# STorM32_NT_logger_v11.net
KiCad netlist of a schematic drawn in EAGLE
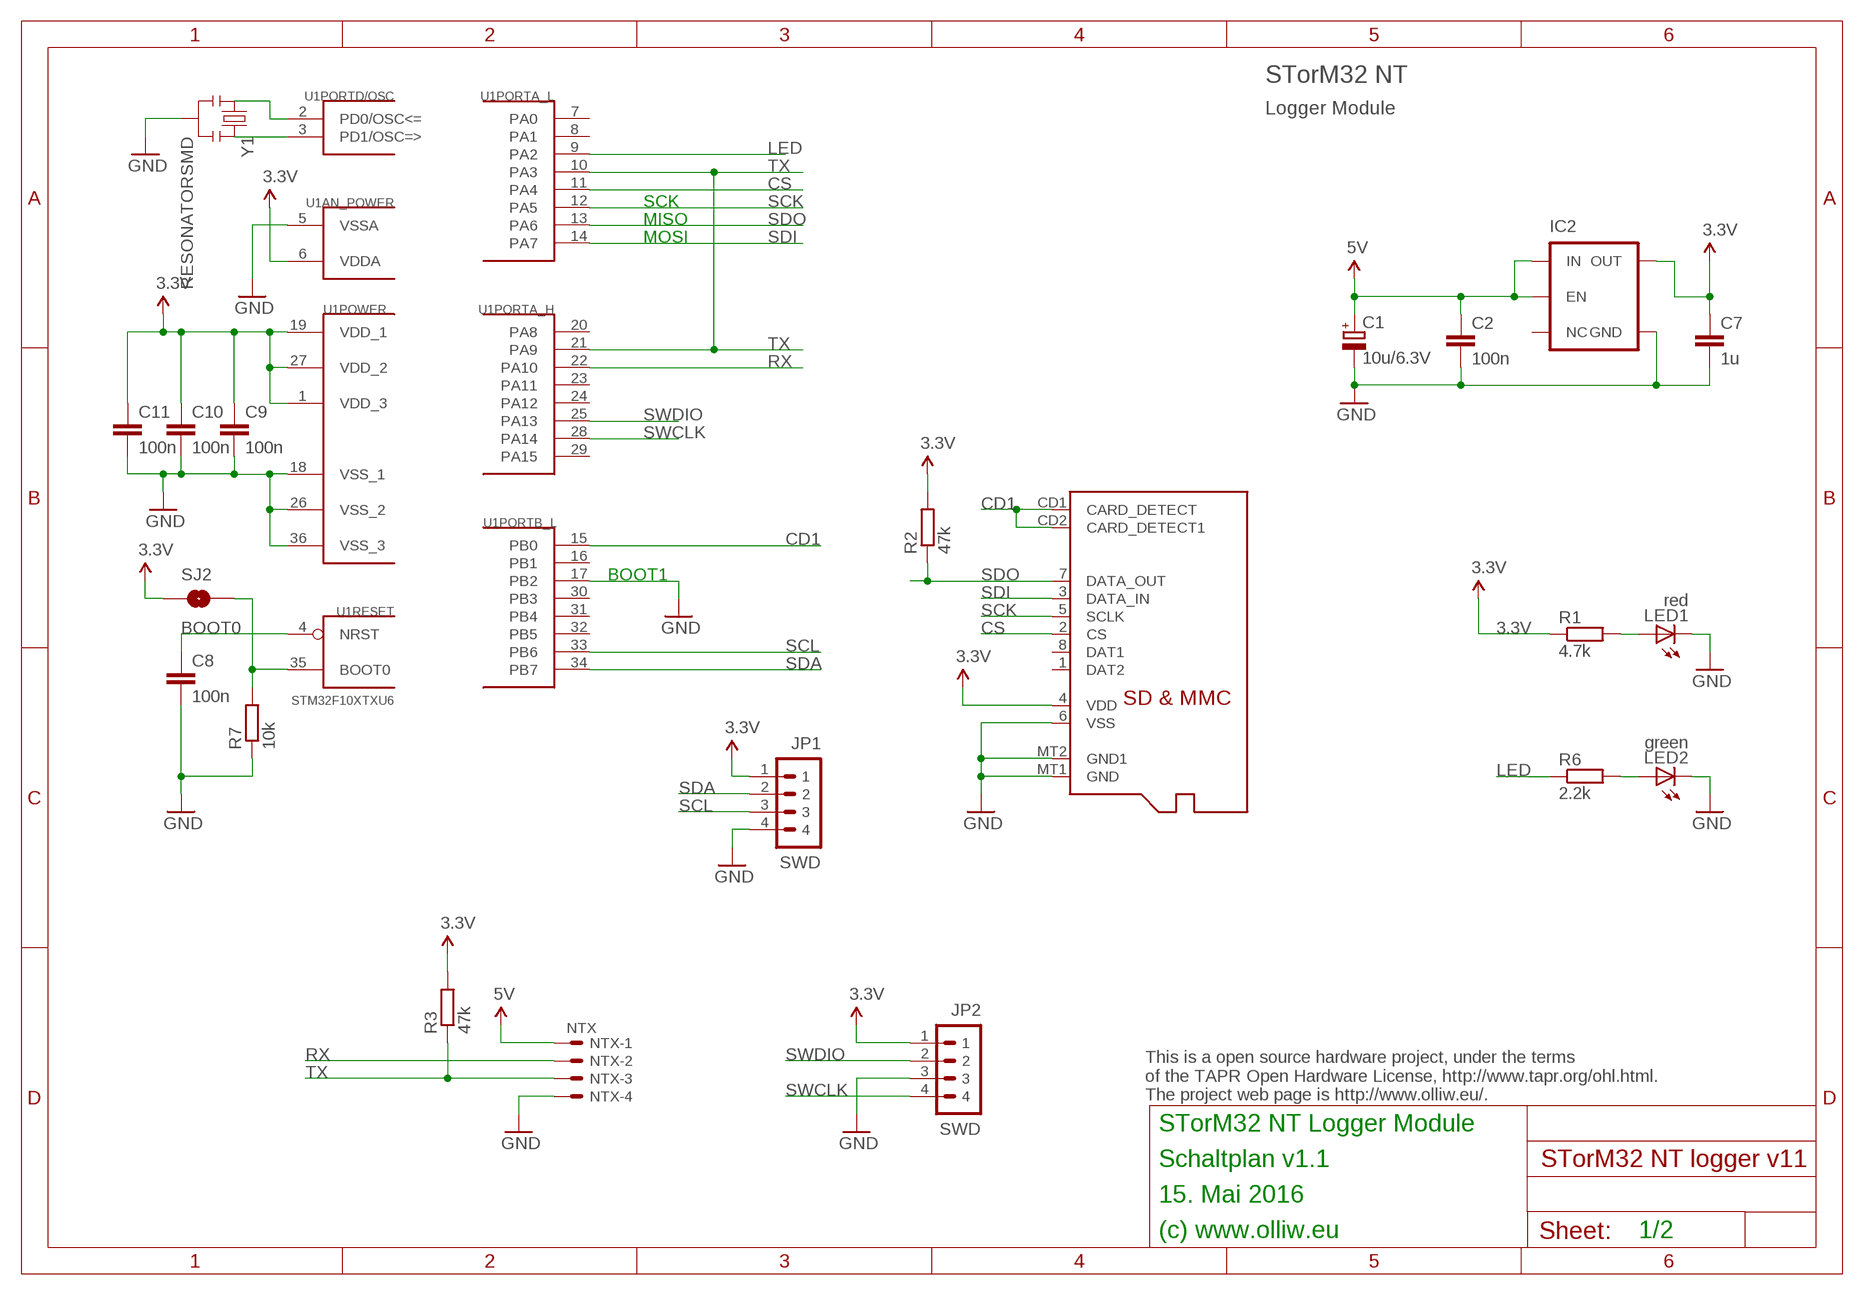
[diagram p0: schematic, sheet 1]

(export (version "E")
  (design (tool "Eeschema 10.0.6"))
  (components
    (comp (ref "C1")
      (value "10u/6.3V")
      (footprint "eagle-import:SMC_B")
      (libsource (lib "eagle-import") (part "CPOL-EUSMCB"))
    )
    (comp (ref "C2")
      (value "100n")
      (footprint "eagle-import:C0603")
      (libsource (lib "eagle-import") (part "C-EUC0603"))
    )
    (comp (ref "C7")
      (value "1u")
      (footprint "eagle-import:C0603")
      (libsource (lib "eagle-import") (part "C-EUC0603"))
    )
    (comp (ref "C8")
      (value "100n")
      (footprint "eagle-import:C0603")
      (libsource (lib "eagle-import") (part "C-EUC0603"))
    )
    (comp (ref "C9")
      (value "100n")
      (footprint "eagle-import:C0603")
      (libsource (lib "eagle-import") (part "C-EUC0603"))
    )
    (comp (ref "C10")
      (value "100n")
      (footprint "eagle-import:C0603")
      (libsource (lib "eagle-import") (part "C-EUC0603"))
    )
    (comp (ref "C11")
      (value "100n")
      (footprint "eagle-import:C0603")
      (libsource (lib "eagle-import") (part "C-EUC0603"))
    )
    (comp (ref "IC2")
      (value "V_REG_TPS76433SOT23-5")
      (footprint "eagle-import:SOT23-5")
      (libsource (lib "eagle-import") (part "V_REG_TPS76433SOT23-5"))
    )
    (comp (ref "JP1")
      (value "SWD")
      (footprint "eagle-import:4X1_1P27_OCT_BILEX")
      (libsource (lib "eagle-import") (part "P4X1_1P27-OCT_BILEX"))
    )
    (comp (ref "JP2")
      (value "SWD")
      (footprint "eagle-import:4X1_1P27_OCT_BILEX")
      (libsource (lib "eagle-import") (part "P4X1_1P27-OCT_BILEX"))
    )
    (comp (ref "LED1")
      (value "red")
      (footprint "eagle-import:CHIPLED_0603")
      (libsource (lib "eagle-import") (part "LEDCHIPLED_0603"))
    )
    (comp (ref "LED2")
      (value "green")
      (footprint "eagle-import:CHIPLED_0603")
      (libsource (lib "eagle-import") (part "LEDCHIPLED_0603"))
    )
    (comp (ref "NTX")
      (value "NTX")
      (footprint "eagle-import:SM04B-SRSS-TB")
      (libsource (lib "eagle-import") (part "?M04B-SRSS-TBS"))
    )
    (comp (ref "R1")
      (value "4.7k")
      (footprint "eagle-import:R0603")
      (libsource (lib "eagle-import") (part "R-EU_R0603"))
    )
    (comp (ref "R2")
      (value "47k")
      (footprint "eagle-import:R0603")
      (libsource (lib "eagle-import") (part "R-EU_R0603"))
    )
    (comp (ref "R3")
      (value "47k")
      (footprint "eagle-import:R0603")
      (libsource (lib "eagle-import") (part "R-EU_R0603"))
    )
    (comp (ref "R6")
      (value "2.2k")
      (footprint "eagle-import:R0603")
      (libsource (lib "eagle-import") (part "R-EU_R0603"))
    )
    (comp (ref "R7")
      (value "10k")
      (footprint "eagle-import:R0603")
      (libsource (lib "eagle-import") (part "R-EU_R0603"))
    )
    (comp (ref "SJ2")
      (value "BOOT0")
      (footprint "eagle-import:SJ_2S-NO")
      (libsource (lib "eagle-import") (part "SOLDERJUMPERNO"))
    )
    (comp (ref "U$1")
      (value "MICROSD")
      (footprint "eagle-import:MICROSD")
      (libsource (lib "eagle-import") (part "MICROSD"))
    )
    (comp (ref "U1")
      (value "STM32F10XTXU6")
      (footprint "eagle-import:VFQFPN36")
      (libsource (lib "eagle-import") (part "STM32F10XTXU6"))
    )
    (comp (ref "Y1")
      (value "RESONATORSMD")
      (footprint "eagle-import:RESONATOR-SMD")
      (libsource (lib "eagle-import") (part "RESONATORSMD"))
    )
  )
  (nets
    (net (code "1") (name "/CD1") (class "Default")
      (node (ref "U$1") (pin "CD1") (pinfunction "CARD_DETECT_CD1") (pintype "passive"))
      (node (ref "U$1") (pin "CD2") (pinfunction "CARD_DETECT1_CD2") (pintype "passive"))
      (node (ref "U1") (pin "15") (pinfunction "PB0_15") (pintype "bidirectional"))
    )
    (net (code "2") (name "/CS") (class "Default")
      (node (ref "U$1") (pin "2") (pinfunction "CS_2") (pintype "input"))
      (node (ref "U1") (pin "11") (pinfunction "PA4_11") (pintype "bidirectional"))
    )
    (net (code "3") (name "/LED") (class "Default")
      (node (ref "R6") (pin "1") (pinfunction "1_1") (pintype "passive"))
      (node (ref "U1") (pin "9") (pinfunction "PA2_9") (pintype "bidirectional"))
    )
    (net (code "4") (name "/RX") (class "Default")
      (node (ref "NTX") (pin "2") (pinfunction "S_2") (pintype "passive"))
      (node (ref "U1") (pin "22") (pinfunction "PA10_22") (pintype "bidirectional"))
    )
    (net (code "5") (name "/SCK") (class "Default")
      (node (ref "U$1") (pin "5") (pinfunction "SCLK_5") (pintype "input"))
      (node (ref "U1") (pin "12") (pinfunction "PA5_12") (pintype "bidirectional"))
    )
    (net (code "6") (name "/SCL") (class "Default")
      (node (ref "JP1") (pin "3") (pinfunction "3_3") (pintype "passive"))
      (node (ref "U1") (pin "33") (pinfunction "PB6_33") (pintype "bidirectional"))
    )
    (net (code "7") (name "/SDA") (class "Default")
      (node (ref "JP1") (pin "2") (pinfunction "2_2") (pintype "passive"))
      (node (ref "U1") (pin "34") (pinfunction "PB7_34") (pintype "bidirectional"))
    )
    (net (code "8") (name "/SDI") (class "Default")
      (node (ref "U$1") (pin "3") (pinfunction "DATA_IN_3") (pintype "input"))
      (node (ref "U1") (pin "14") (pinfunction "PA7_14") (pintype "bidirectional"))
    )
    (net (code "9") (name "/SDO") (class "Default")
      (node (ref "R2") (pin "1") (pinfunction "1_1") (pintype "passive"))
      (node (ref "U$1") (pin "7") (pinfunction "DATA_OUT_7") (pintype "output"))
      (node (ref "U1") (pin "13") (pinfunction "PA6_13") (pintype "bidirectional"))
    )
    (net (code "10") (name "/SWCLK") (class "Default")
      (node (ref "JP2") (pin "4") (pinfunction "4_4") (pintype "passive"))
      (node (ref "U1") (pin "28") (pinfunction "PA14_28") (pintype "bidirectional"))
    )
    (net (code "11") (name "/SWDIO") (class "Default")
      (node (ref "JP2") (pin "2") (pinfunction "2_2") (pintype "passive"))
      (node (ref "U1") (pin "25") (pinfunction "PA13_25") (pintype "bidirectional"))
    )
    (net (code "12") (name "/TX") (class "Default")
      (node (ref "NTX") (pin "3") (pinfunction "S_3") (pintype "passive"))
      (node (ref "R3") (pin "1") (pinfunction "1_1") (pintype "passive"))
      (node (ref "U1") (pin "10") (pinfunction "PA3_10") (pintype "bidirectional"))
      (node (ref "U1") (pin "21") (pinfunction "PA9_21") (pintype "bidirectional"))
    )
    (net (code "13") (name "3.3V") (class "Default")
      (node (ref "C10") (pin "1") (pinfunction "1_1") (pintype "passive"))
      (node (ref "C11") (pin "1") (pinfunction "1_1") (pintype "passive"))
      (node (ref "C7") (pin "1") (pinfunction "1_1") (pintype "passive"))
      (node (ref "C9") (pin "1") (pinfunction "1_1") (pintype "passive"))
      (node (ref "IC2") (pin "5") (pinfunction "OUT_5") (pintype "passive"))
      (node (ref "JP1") (pin "1") (pinfunction "1_1") (pintype "passive"))
      (node (ref "JP2") (pin "1") (pinfunction "1_1") (pintype "passive"))
      (node (ref "R1") (pin "1") (pinfunction "1_1") (pintype "passive"))
      (node (ref "R2") (pin "2") (pinfunction "2_2") (pintype "passive"))
      (node (ref "R3") (pin "2") (pinfunction "2_2") (pintype "passive"))
      (node (ref "SJ2") (pin "1") (pinfunction "1_1") (pintype "passive"))
      (node (ref "U$1") (pin "4") (pinfunction "VDD_4") (pintype "power_in"))
      (node (ref "U1") (pin "1") (pinfunction "VDD_3_1") (pintype "power_in"))
      (node (ref "U1") (pin "19") (pinfunction "VDD_1_19") (pintype "power_in"))
      (node (ref "U1") (pin "27") (pinfunction "VDD_2_27") (pintype "power_in"))
      (node (ref "U1") (pin "6") (pinfunction "VDDA_6") (pintype "power_in"))
    )
    (net (code "14") (name "5V") (class "Default")
      (node (ref "C1") (pin "+") (pinfunction "+_+") (pintype "passive"))
      (node (ref "C2") (pin "1") (pinfunction "1_1") (pintype "passive"))
      (node (ref "IC2") (pin "1") (pinfunction "IN_1") (pintype "input"))
      (node (ref "IC2") (pin "3") (pinfunction "EN_3") (pintype "input"))
      (node (ref "NTX") (pin "1") (pinfunction "S_1") (pintype "passive"))
    )
    (net (code "15") (name "GND") (class "Default")
      (node (ref "C1") (pin "-") (pinfunction "-_-") (pintype "passive"))
      (node (ref "C10") (pin "2") (pinfunction "2_2") (pintype "passive"))
      (node (ref "C11") (pin "2") (pinfunction "2_2") (pintype "passive"))
      (node (ref "C2") (pin "2") (pinfunction "2_2") (pintype "passive"))
      (node (ref "C7") (pin "2") (pinfunction "2_2") (pintype "passive"))
      (node (ref "C8") (pin "2") (pinfunction "2_2") (pintype "passive"))
      (node (ref "C9") (pin "2") (pinfunction "2_2") (pintype "passive"))
      (node (ref "IC2") (pin "2") (pinfunction "GND_2") (pintype "input"))
      (node (ref "JP1") (pin "4") (pinfunction "4_4") (pintype "passive"))
      (node (ref "JP2") (pin "3") (pinfunction "3_3") (pintype "passive"))
      (node (ref "LED1") (pin "C") (pinfunction "C_C") (pintype "passive"))
      (node (ref "LED2") (pin "C") (pinfunction "C_C") (pintype "passive"))
      (node (ref "NTX") (pin "4") (pinfunction "S_4") (pintype "passive"))
      (node (ref "R7") (pin "1") (pinfunction "1_1") (pintype "passive"))
      (node (ref "U$1") (pin "6") (pinfunction "VSS_6") (pintype "power_in"))
      (node (ref "U$1") (pin "MT1") (pinfunction "GND_MT1") (pintype "power_in"))
      (node (ref "U$1") (pin "MT2") (pinfunction "GND1_MT2") (pintype "power_in"))
      (node (ref "U1") (pin "17") (pinfunction "PB2_17") (pintype "bidirectional"))
      (node (ref "U1") (pin "18") (pinfunction "VSS_1_18") (pintype "power_in"))
      (node (ref "U1") (pin "26") (pinfunction "VSS_2_26") (pintype "power_in"))
      (node (ref "U1") (pin "36") (pinfunction "VSS_3_36") (pintype "power_in"))
      (node (ref "U1") (pin "5") (pinfunction "VSSA_5") (pintype "power_in"))
      (node (ref "Y1") (pin "2") (pinfunction "2_2") (pintype "passive"))
    )
    (net (code "16") (name "Net-(LED1-PadA)") (class "Default")
      (node (ref "LED1") (pin "A") (pinfunction "A_A") (pintype "passive"))
      (node (ref "R1") (pin "2") (pinfunction "2_2") (pintype "passive"))
    )
    (net (code "17") (name "Net-(LED2-PadA)") (class "Default")
      (node (ref "LED2") (pin "A") (pinfunction "A_A") (pintype "passive"))
      (node (ref "R6") (pin "2") (pinfunction "2_2") (pintype "passive"))
    )
    (net (code "18") (name "Net-(U1E-PD0{slash}OSC<=)") (class "Default")
      (node (ref "U1") (pin "2") (pinfunction "PD0/OSC<=_2") (pintype "bidirectional"))
      (node (ref "Y1") (pin "1") (pinfunction "1_1") (pintype "passive"))
    )
    (net (code "19") (name "Net-(U1E-PD1{slash}OSC=>)") (class "Default")
      (node (ref "U1") (pin "3") (pinfunction "PD1/OSC=>_3") (pintype "bidirectional"))
      (node (ref "Y1") (pin "3") (pinfunction "3_3") (pintype "passive"))
    )
    (net (code "20") (name "Net-(U1G-BOOT0)") (class "Default")
      (node (ref "R7") (pin "2") (pinfunction "2_2") (pintype "passive"))
      (node (ref "SJ2") (pin "2") (pinfunction "2_2") (pintype "passive"))
      (node (ref "U1") (pin "35") (pinfunction "BOOT0_35") (pintype "input"))
    )
    (net (code "21") (name "Net-(U1G-NRST)") (class "Default")
      (node (ref "C8") (pin "1") (pinfunction "1_1") (pintype "passive"))
      (node (ref "U1") (pin "4") (pinfunction "NRST_4") (pintype "input"))
    )
    (net (code "22") (name "unconnected-(IC2-NC-Pad4)") (class "Default")
      (node (ref "IC2") (pin "4") (pinfunction "NC_4") (pintype "input"))
    )
    (net (code "23") (name "unconnected-(U$1-DAT1-Pad8)") (class "Default")
      (node (ref "U$1") (pin "8") (pinfunction "DAT1_8") (pintype "bidirectional"))
    )
    (net (code "24") (name "unconnected-(U$1-DAT2-Pad1)") (class "Default")
      (node (ref "U$1") (pin "1") (pinfunction "DAT2_1") (pintype "bidirectional"))
    )
    (net (code "25") (name "unconnected-(U1B-PA8-Pad20)") (class "Default")
      (node (ref "U1") (pin "20") (pinfunction "PA8_20") (pintype "bidirectional"))
    )
    (net (code "26") (name "unconnected-(U1B-PA11-Pad23)") (class "Default")
      (node (ref "U1") (pin "23") (pinfunction "PA11_23") (pintype "bidirectional"))
    )
    (net (code "27") (name "unconnected-(U1B-PA12-Pad24)") (class "Default")
      (node (ref "U1") (pin "24") (pinfunction "PA12_24") (pintype "bidirectional"))
    )
    (net (code "28") (name "unconnected-(U1B-PA15-Pad29)") (class "Default")
      (node (ref "U1") (pin "29") (pinfunction "PA15_29") (pintype "bidirectional"))
    )
    (net (code "29") (name "unconnected-(U1C-PA0-Pad7)") (class "Default")
      (node (ref "U1") (pin "7") (pinfunction "PA0_7") (pintype "bidirectional"))
    )
    (net (code "30") (name "unconnected-(U1C-PA1-Pad8)") (class "Default")
      (node (ref "U1") (pin "8") (pinfunction "PA1_8") (pintype "bidirectional"))
    )
    (net (code "31") (name "unconnected-(U1D-PB1-Pad16)") (class "Default")
      (node (ref "U1") (pin "16") (pinfunction "PB1_16") (pintype "bidirectional"))
    )
    (net (code "32") (name "unconnected-(U1D-PB3-Pad30)") (class "Default")
      (node (ref "U1") (pin "30") (pinfunction "PB3_30") (pintype "bidirectional"))
    )
    (net (code "33") (name "unconnected-(U1D-PB4-Pad31)") (class "Default")
      (node (ref "U1") (pin "31") (pinfunction "PB4_31") (pintype "bidirectional"))
    )
    (net (code "34") (name "unconnected-(U1D-PB5-Pad32)") (class "Default")
      (node (ref "U1") (pin "32") (pinfunction "PB5_32") (pintype "bidirectional"))
    )
  )
)
